# pt100.net
KiCad netlist of a schematic drawn in Altium Designer
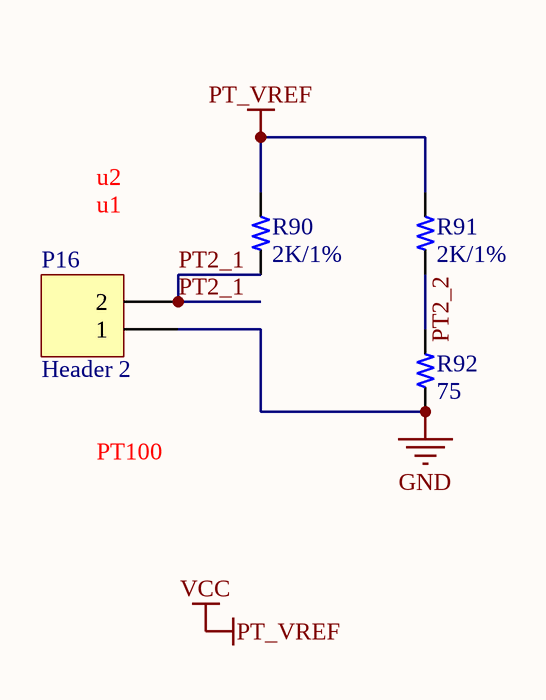
[diagram p0: pt100.SchDoc]

(export (version "E")
  (design (tool "Eeschema 10.0.6"))
  (components
    (comp (ref "P16")
      (value "Header 2")
      (footprint "KF250NH-3.5-2P")
      (fields (field (name "PUBLISHER") "Altium Limited"))
      (libsource (lib "Miscellaneous Connectors") (part "Header 2"))
    )
    (comp (ref "R90") (value "2K/1%") (footprint "0603R") (libsource (lib "JRJ_1") (part "R")))
    (comp (ref "R91") (value "2K/1%") (footprint "0603R") (libsource (lib "JRJ_1") (part "R")))
    (comp (ref "R92") (value "75") (footprint "0603R") (libsource (lib "JRJ_1") (part "R")))
  )
  (nets
    (net (code "1") (name "/PT2_1") (class "Default")
      (node (ref "P16") (pin "2") (pinfunction "2_2") (pintype "passive"))
      (node (ref "R90") (pin "1") (pintype "passive"))
    )
    (net (code "2") (name "/PT2_2") (class "Default")
      (node (ref "R91") (pin "1") (pintype "passive"))
      (node (ref "R92") (pin "2") (pintype "passive"))
    )
    (net (code "3") (name "GND") (class "Default")
      (node (ref "P16") (pin "1") (pinfunction "1_1") (pintype "passive"))
      (node (ref "R92") (pin "1") (pintype "passive"))
    )
    (net (code "4") (name "PT_VREF") (class "Default")
      (node (ref "R90") (pin "2") (pintype "passive"))
      (node (ref "R91") (pin "2") (pintype "passive"))
    )
  )
)
